# SDP21_Main_Board_Schematic.net
KiCad netlist of a schematic drawn in Altium Designer
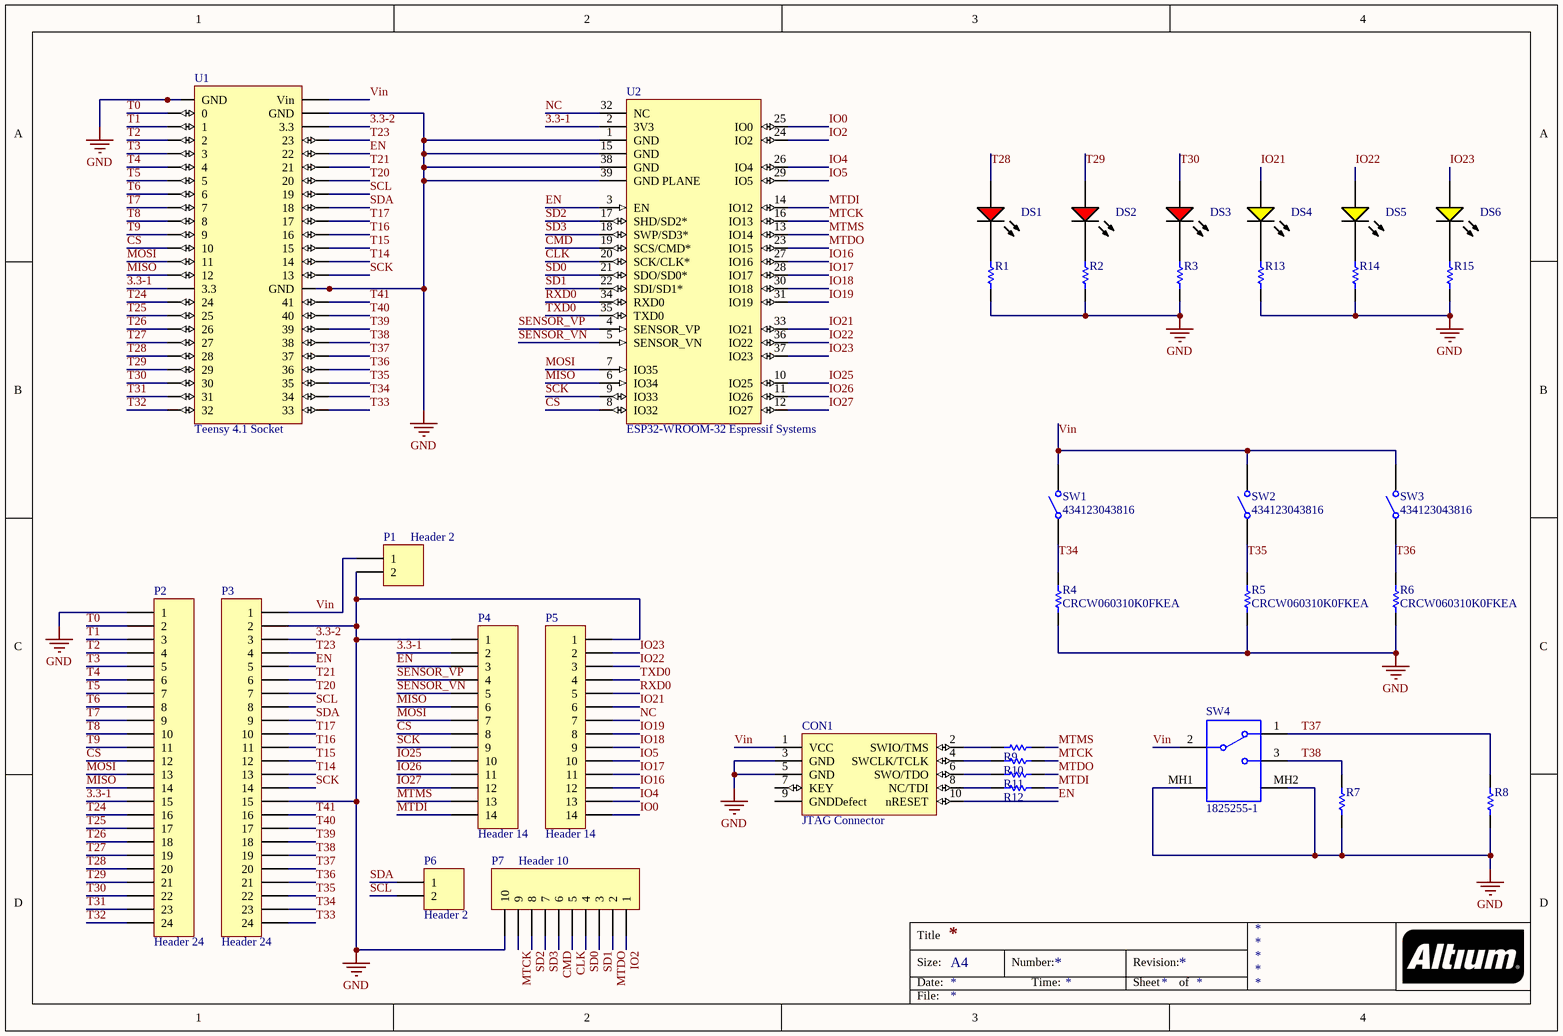
[diagram p0: SDP21_Main_Board_Schematic.SchDoc]

(export (version "E")
  (design (tool "Eeschema 10.0.6"))
  (components
    (comp (ref "CON1")
      (value "JTAG Connector")
      (footprint "5x2 - 50mil")
      (libsource (lib "SDP21_Main_Board_Schematic_Library") (part "JTAG Connector"))
    )
    (comp (ref "DS1")
      (value "TLMS1000-GS08")
      (footprint "VISH-TLMS1000_V")
      (description "Low Current LED, 40 mW, 1.8 V, -40 to 100 degC, 2-Pin SMD (0603), RoHS, Tape and Reel")
      (fields (field (name "MANUFACTURER") "Vishay"))
      (libsource (lib "Altium Content Vault") (part "LED-RED-AK-2"))
    )
    (comp (ref "DS2")
      (value "TLMS1000-GS08")
      (footprint "VISH-TLMS1000_V")
      (description "Low Current LED, 40 mW, 1.8 V, -40 to 100 degC, 2-Pin SMD (0603), RoHS, Tape and Reel")
      (fields (field (name "MANUFACTURER") "Vishay"))
      (libsource (lib "Altium Content Vault") (part "LED-RED-AK-2"))
    )
    (comp (ref "DS3")
      (value "TLMS1000-GS08")
      (footprint "VISH-TLMS1000_V")
      (description "Low Current LED, 40 mW, 1.8 V, -40 to 100 degC, 2-Pin SMD (0603), RoHS, Tape and Reel")
      (fields (field (name "MANUFACTURER") "Vishay"))
      (libsource (lib "Altium Content Vault") (part "LED-RED-AK-2"))
    )
    (comp (ref "DS4")
      (value "TLMY1000-GS08")
      (footprint "VISH-TLMY1000_V")
      (description "Low Current LED, 40 mW, -40 to 100 degC, 2-Pin SMD, RoHS, Tape and Reel")
      (fields (field (name "MANUFACTURER") "Vishay"))
      (libsource (lib "Altium Content Vault") (part "LED-YELLOW-AK-2"))
    )
    (comp (ref "DS5")
      (value "TLMY1000-GS08")
      (footprint "VISH-TLMY1000_V")
      (description "Low Current LED, 40 mW, -40 to 100 degC, 2-Pin SMD, RoHS, Tape and Reel")
      (fields (field (name "MANUFACTURER") "Vishay"))
      (libsource (lib "Altium Content Vault") (part "LED-YELLOW-AK-2"))
    )
    (comp (ref "DS6")
      (value "TLMY1000-GS08")
      (footprint "VISH-TLMY1000_V")
      (description "Low Current LED, 40 mW, -40 to 100 degC, 2-Pin SMD, RoHS, Tape and Reel")
      (fields (field (name "MANUFACTURER") "Vishay"))
      (libsource (lib "Altium Content Vault") (part "LED-YELLOW-AK-2"))
    )
    (comp (ref "P1")
      (value "Header 2")
      (footprint "HDR1X2")
      (description "Header, 2-Pin")
      (fields (field (name "PUBLISHER") "Altium Limited"))
      (libsource (lib "Miscellaneous Connectors") (part "Header 2"))
    )
    (comp (ref "P2")
      (value "Header 24")
      (footprint "HDR1X24")
      (description "Header, 24-Pin")
      (fields (field (name "PUBLISHER") "Altium Limited"))
      (libsource (lib "") (part "Header 24_1"))
    )
    (comp (ref "P3")
      (value "Header 24")
      (footprint "HDR1X24")
      (description "Header, 24-Pin")
      (fields (field (name "PUBLISHER") "Altium Limited"))
      (libsource (lib "Miscellaneous Connectors") (part "Header 24"))
    )
    (comp (ref "P4")
      (value "Header 14")
      (footprint "HDR1X14")
      (description "Header, 14-Pin")
      (fields (field (name "PUBLISHER") "Altium Limited"))
      (libsource (lib "") (part "Header 14_1"))
    )
    (comp (ref "P5")
      (value "Header 14")
      (footprint "HDR1X14")
      (description "Header, 14-Pin")
      (fields (field (name "PUBLISHER") "Altium Limited"))
      (libsource (lib "Miscellaneous Connectors") (part "Header 14"))
    )
    (comp (ref "P6")
      (value "Header 2")
      (footprint "HDR1X2")
      (description "Header, 2-Pin")
      (fields (field (name "PUBLISHER") "Altium Limited"))
      (libsource (lib "Miscellaneous Connectors") (part "Header 2"))
    )
    (comp (ref "P7")
      (value "Header 10")
      (footprint "HDR1X10")
      (description "Header, 10-Pin")
      (fields (field (name "PUBLISHER") "Altium Limited"))
      (libsource (lib "Miscellaneous Connectors") (part "Header 10"))
    )
    (comp (ref "R1")
      (value "RR1220P-331-D")
      (footprint "RESC2013X50X40LL20T20")
      (fields (field (name "MANUFACTURER") "Susumu"))
      (libsource (lib "Altium Content Vault") (part "RES"))
    )
    (comp (ref "R2")
      (value "RR1220P-331-D")
      (footprint "RESC2013X50X40LL20T20")
      (fields (field (name "MANUFACTURER") "Susumu"))
      (libsource (lib "Altium Content Vault") (part "RES"))
    )
    (comp (ref "R3")
      (value "RR1220P-331-D")
      (footprint "RESC2013X50X40LL20T20")
      (fields (field (name "MANUFACTURER") "Susumu"))
      (libsource (lib "Altium Content Vault") (part "RES"))
    )
    (comp (ref "R4")
      (value "CRCW060310K0FKEA")
      (footprint "RESC1609X50X30NL8T20")
      (description "Chip Resistor, 10 KOhm, +/- 1%, 100 mW, -55 to 155 degC, 0603 (1608 Metric), RoHS, Tape and Reel")
      (fields (field (name "MANUFACTURER") "Vishay Semiconductor"))
      (libsource (lib "Altium Content Vault") (part "RES-2"))
    )
    (comp (ref "R5")
      (value "CRCW060310K0FKEA")
      (footprint "RESC1609X50X30NL8T20")
      (description "Chip Resistor, 10 KOhm, +/- 1%, 100 mW, -55 to 155 degC, 0603 (1608 Metric), RoHS, Tape and Reel")
      (fields (field (name "MANUFACTURER") "Vishay Semiconductor"))
      (libsource (lib "Altium Content Vault") (part "RES-2"))
    )
    (comp (ref "R6")
      (value "CRCW060310K0FKEA")
      (footprint "RESC1609X50X30NL8T20")
      (description "Chip Resistor, 10 KOhm, +/- 1%, 100 mW, -55 to 155 degC, 0603 (1608 Metric), RoHS, Tape and Reel")
      (fields (field (name "MANUFACTURER") "Vishay Semiconductor"))
      (libsource (lib "Altium Content Vault") (part "RES-2"))
    )
    (comp (ref "R7")
      (value "CRCW060310K0FKEA")
      (footprint "RESC1609X50X30NL8T20")
      (description "Chip Resistor, 10 KOhm, +/- 1%, 100 mW, -55 to 155 degC, 0603 (1608 Metric), RoHS, Tape and Reel")
      (fields (field (name "MANUFACTURER") "Vishay Semiconductor"))
      (libsource (lib "Altium Content Vault") (part "RES-2"))
    )
    (comp (ref "R8")
      (value "CRCW060310K0FKEA")
      (footprint "RESC1609X50X30NL8T20")
      (description "Chip Resistor, 10 KOhm, +/- 1%, 100 mW, -55 to 155 degC, 0603 (1608 Metric), RoHS, Tape and Reel")
      (fields (field (name "MANUFACTURER") "Vishay Semiconductor"))
      (libsource (lib "Altium Content Vault") (part "RES-2"))
    )
    (comp (ref "R9")
      (value "CRCW0603100RFKEA")
      (footprint "RESC1609X50X30NL10T20")
      (fields (field (name "MANUFACTURER") "Vishay Dale"))
      (libsource (lib "Altium Content Vault") (part "RES"))
    )
    (comp (ref "R10")
      (value "CRCW0603100RFKEA")
      (footprint "RESC1609X50X30NL10T20")
      (fields (field (name "MANUFACTURER") "Vishay Dale"))
      (libsource (lib "Altium Content Vault") (part "RES"))
    )
    (comp (ref "R11")
      (value "CRCW0603100RFKEA")
      (footprint "RESC1609X50X30NL10T20")
      (fields (field (name "MANUFACTURER") "Vishay Dale"))
      (libsource (lib "Altium Content Vault") (part "RES"))
    )
    (comp (ref "R12")
      (value "CRCW0603100RFKEA")
      (footprint "RESC1609X50X30NL10T20")
      (fields (field (name "MANUFACTURER") "Vishay Dale"))
      (libsource (lib "Altium Content Vault") (part "RES"))
    )
    (comp (ref "R13")
      (value "RR1220P-331-D")
      (footprint "RESC2013X50X40LL20T20")
      (fields (field (name "MANUFACTURER") "Susumu"))
      (libsource (lib "Altium Content Vault") (part "RES"))
    )
    (comp (ref "R14")
      (value "RR1220P-331-D")
      (footprint "RESC2013X50X40LL20T20")
      (fields (field (name "MANUFACTURER") "Susumu"))
      (libsource (lib "Altium Content Vault") (part "RES"))
    )
    (comp (ref "R15")
      (value "RR1220P-331-D")
      (footprint "RESC2013X50X40LL20T20")
      (fields (field (name "MANUFACTURER") "Susumu"))
      (libsource (lib "Altium Content Vault") (part "RES"))
    )
    (comp (ref "SW1")
      (value "434123043816")
      (footprint "434123043816")
      (description "WS-TASV J-Bend SMD Tact Switch 6.0X3.5 mm")
      (fields (field (name "MANUFACTURER") "Wuerth Elektronik"))
      (libsource (lib "Altium Content Vault") (part "WE-TACT-SW-2"))
    )
    (comp (ref "SW2")
      (value "434123043816")
      (footprint "434123043816")
      (description "WS-TASV J-Bend SMD Tact Switch 6.0X3.5 mm")
      (fields (field (name "MANUFACTURER") "Wuerth Elektronik"))
      (libsource (lib "Altium Content Vault") (part "WE-TACT-SW-2"))
    )
    (comp (ref "SW3")
      (value "434123043816")
      (footprint "434123043816")
      (description "WS-TASV J-Bend SMD Tact Switch 6.0X3.5 mm")
      (fields (field (name "MANUFACTURER") "Wuerth Elektronik"))
      (libsource (lib "Altium Content Vault") (part "WE-TACT-SW-2"))
    )
    (comp (ref "SW4")
      (value "1825255-1")
      (footprint "TECO-1825255-1_V")
      (description "Slide Switch, SPDT, 125 V, -20 to 85 degC, 5-Pin THD, RoHS, Tray")
      (fields (field (name "MANUFACTURER") "TE Connectivity"))
      (libsource (lib "Altium Content Vault") (part "SW-SPDT-3_C"))
    )
    (comp (ref "U1")
      (value "Teensy 4.1 Socket")
      (footprint "Teensy 4.1 Socket")
      (description "Teensy 4.1")
      (libsource (lib "SDP21_Main_Board_Schematic_Library") (part "Teensy 4.1 Socket"))
    )
    (comp (ref "U2")
      (value "ESP32-WROOM-32 Espressif Systems")
      (footprint "Espressif ESP32 Castellated")
      (description "ESP32 BGA mounted on PCB w/ castellated holes")
      (libsource (lib "SDP21_Main_Board_Schematic_Library") (part "ESP32-WROOM-32 Espressif Systems"))
    )
  )
  (nets
    (net (code "1") (name "/3.3-1") (class "Default")
      (node (ref "P2") (pin "15") (pinfunction "15_15") (pintype "passive"))
      (node (ref "P4") (pin "2") (pinfunction "2_2") (pintype "passive"))
      (node (ref "U1") (pin "3.3-1") (pinfunction "3.3_3.3-1") (pintype "power_in"))
      (node (ref "U2") (pin "2") (pinfunction "3V3_2") (pintype "power_in"))
    )
    (net (code "2") (name "/3.3-2") (class "Default")
      (node (ref "P3") (pin "3") (pinfunction "3_3") (pintype "passive"))
      (node (ref "U1") (pin "3.3-2") (pinfunction "3.3_3.3-2") (pintype "power_in"))
    )
    (net (code "3") (name "/CLK") (class "Default")
      (node (ref "P7") (pin "5") (pinfunction "5_5") (pintype "passive"))
      (node (ref "U2") (pin "20") (pinfunction "SCK/CLK*_20") (pintype "bidirectional"))
    )
    (net (code "4") (name "/CMD") (class "Default")
      (node (ref "P7") (pin "6") (pinfunction "6_6") (pintype "passive"))
      (node (ref "U2") (pin "19") (pinfunction "SCS/CMD*_19") (pintype "bidirectional"))
    )
    (net (code "5") (name "/CS") (class "Default")
      (node (ref "P2") (pin "12") (pinfunction "12_12") (pintype "passive"))
      (node (ref "P4") (pin "8") (pinfunction "8_8") (pintype "passive"))
      (node (ref "U1") (pin "10") (pinfunction "10_10") (pintype "bidirectional"))
      (node (ref "U2") (pin "8") (pinfunction "IO32_8") (pintype "bidirectional"))
    )
    (net (code "6") (name "/EN") (class "Default")
      (node (ref "CON1") (pin "10") (pinfunction "nRESET_10") (pintype "bidirectional"))
      (node (ref "P3") (pin "5") (pinfunction "5_5") (pintype "passive"))
      (node (ref "P4") (pin "3") (pinfunction "3_3") (pintype "passive"))
      (node (ref "U1") (pin "22") (pinfunction "22_22") (pintype "bidirectional"))
      (node (ref "U2") (pin "3") (pinfunction "EN_3") (pintype "input"))
    )
    (net (code "7") (name "/IO0") (class "Default")
      (node (ref "P5") (pin "14") (pinfunction "14_14") (pintype "passive"))
      (node (ref "U2") (pin "25") (pinfunction "IO0_25") (pintype "bidirectional"))
    )
    (net (code "8") (name "/IO2") (class "Default")
      (node (ref "P7") (pin "1") (pinfunction "1_1") (pintype "passive"))
      (node (ref "U2") (pin "24") (pinfunction "IO2_24") (pintype "bidirectional"))
    )
    (net (code "9") (name "/IO4") (class "Default")
      (node (ref "P5") (pin "13") (pinfunction "13_13") (pintype "passive"))
      (node (ref "U2") (pin "26") (pinfunction "IO4_26") (pintype "bidirectional"))
    )
    (net (code "10") (name "/IO5") (class "Default")
      (node (ref "P5") (pin "10") (pinfunction "10_10") (pintype "passive"))
      (node (ref "U2") (pin "29") (pinfunction "IO5_29") (pintype "bidirectional"))
    )
    (net (code "11") (name "/IO16") (class "Default")
      (node (ref "P5") (pin "12") (pinfunction "12_12") (pintype "passive"))
      (node (ref "U2") (pin "27") (pinfunction "IO16_27") (pintype "bidirectional"))
    )
    (net (code "12") (name "/IO17") (class "Default")
      (node (ref "P5") (pin "11") (pinfunction "11_11") (pintype "passive"))
      (node (ref "U2") (pin "28") (pinfunction "IO17_28") (pintype "bidirectional"))
    )
    (net (code "13") (name "/IO18") (class "Default")
      (node (ref "P5") (pin "9") (pinfunction "9_9") (pintype "passive"))
      (node (ref "U2") (pin "30") (pinfunction "IO18_30") (pintype "bidirectional"))
    )
    (net (code "14") (name "/IO19") (class "Default")
      (node (ref "P5") (pin "8") (pinfunction "8_8") (pintype "passive"))
      (node (ref "U2") (pin "31") (pinfunction "IO19_31") (pintype "bidirectional"))
    )
    (net (code "15") (name "/IO21") (class "Default")
      (node (ref "DS4") (pin "1") (pinfunction "A_1") (pintype "passive"))
      (node (ref "P5") (pin "6") (pinfunction "6_6") (pintype "passive"))
      (node (ref "U2") (pin "33") (pinfunction "IO21_33") (pintype "bidirectional"))
    )
    (net (code "16") (name "/IO22") (class "Default")
      (node (ref "DS5") (pin "1") (pinfunction "A_1") (pintype "passive"))
      (node (ref "P5") (pin "3") (pinfunction "3_3") (pintype "passive"))
      (node (ref "U2") (pin "36") (pinfunction "IO22_36") (pintype "bidirectional"))
    )
    (net (code "17") (name "/IO23") (class "Default")
      (node (ref "DS6") (pin "1") (pinfunction "A_1") (pintype "passive"))
      (node (ref "P5") (pin "2") (pinfunction "2_2") (pintype "passive"))
      (node (ref "U2") (pin "37") (pinfunction "IO23_37") (pintype "bidirectional"))
    )
    (net (code "18") (name "/IO25") (class "Default")
      (node (ref "P4") (pin "10") (pinfunction "10_10") (pintype "passive"))
      (node (ref "U2") (pin "10") (pinfunction "IO25_10") (pintype "bidirectional"))
    )
    (net (code "19") (name "/IO26") (class "Default")
      (node (ref "P4") (pin "11") (pinfunction "11_11") (pintype "passive"))
      (node (ref "U2") (pin "11") (pinfunction "IO26_11") (pintype "bidirectional"))
    )
    (net (code "20") (name "/IO27") (class "Default")
      (node (ref "P4") (pin "12") (pinfunction "12_12") (pintype "passive"))
      (node (ref "U2") (pin "12") (pinfunction "IO27_12") (pintype "bidirectional"))
    )
    (net (code "21") (name "/MISO") (class "Default")
      (node (ref "P2") (pin "14") (pinfunction "14_14") (pintype "passive"))
      (node (ref "P4") (pin "6") (pinfunction "6_6") (pintype "passive"))
      (node (ref "U1") (pin "12") (pinfunction "12_12") (pintype "bidirectional"))
      (node (ref "U2") (pin "6") (pinfunction "IO34_6") (pintype "input"))
    )
    (net (code "22") (name "/MOSI") (class "Default")
      (node (ref "P2") (pin "13") (pinfunction "13_13") (pintype "passive"))
      (node (ref "P4") (pin "7") (pinfunction "7_7") (pintype "passive"))
      (node (ref "U1") (pin "11") (pinfunction "11_11") (pintype "bidirectional"))
      (node (ref "U2") (pin "7") (pinfunction "IO35_7") (pintype "input"))
    )
    (net (code "23") (name "/MTCK") (class "Default")
      (node (ref "P7") (pin "9") (pinfunction "9_9") (pintype "passive"))
      (node (ref "R10") (pin "2") (pinfunction "2_2") (pintype "passive"))
      (node (ref "U2") (pin "16") (pinfunction "IO13_16") (pintype "bidirectional"))
    )
    (net (code "24") (name "/MTDI") (class "Default")
      (node (ref "P4") (pin "14") (pinfunction "14_14") (pintype "passive"))
      (node (ref "R12") (pin "2") (pinfunction "2_2") (pintype "passive"))
      (node (ref "U2") (pin "14") (pinfunction "IO12_14") (pintype "bidirectional"))
    )
    (net (code "25") (name "/MTDO") (class "Default")
      (node (ref "P7") (pin "2") (pinfunction "2_2") (pintype "passive"))
      (node (ref "R11") (pin "2") (pinfunction "2_2") (pintype "passive"))
      (node (ref "U2") (pin "23") (pinfunction "IO15_23") (pintype "bidirectional"))
    )
    (net (code "26") (name "/MTMS") (class "Default")
      (node (ref "P4") (pin "13") (pinfunction "13_13") (pintype "passive"))
      (node (ref "R9") (pin "2") (pinfunction "2_2") (pintype "passive"))
      (node (ref "U2") (pin "13") (pinfunction "IO14_13") (pintype "bidirectional"))
    )
    (net (code "27") (name "/NC") (class "Default")
      (node (ref "P5") (pin "7") (pinfunction "7_7") (pintype "passive"))
      (node (ref "U2") (pin "32") (pinfunction "NC_32") (pintype "passive"))
    )
    (net (code "28") (name "/RXD0") (class "Default")
      (node (ref "P5") (pin "5") (pinfunction "5_5") (pintype "passive"))
      (node (ref "U2") (pin "34") (pinfunction "RXD0_34") (pintype "bidirectional"))
    )
    (net (code "29") (name "/SCK") (class "Default")
      (node (ref "P3") (pin "14") (pinfunction "14_14") (pintype "passive"))
      (node (ref "P4") (pin "9") (pinfunction "9_9") (pintype "passive"))
      (node (ref "U1") (pin "13") (pinfunction "13_13") (pintype "bidirectional"))
      (node (ref "U2") (pin "9") (pinfunction "IO33_9") (pintype "bidirectional"))
    )
    (net (code "30") (name "/SCL") (class "Default")
      (node (ref "P3") (pin "8") (pinfunction "8_8") (pintype "passive"))
      (node (ref "P6") (pin "2") (pinfunction "2_2") (pintype "passive"))
      (node (ref "U1") (pin "19") (pinfunction "19_19") (pintype "bidirectional"))
    )
    (net (code "31") (name "/SD0") (class "Default")
      (node (ref "P7") (pin "4") (pinfunction "4_4") (pintype "passive"))
      (node (ref "U2") (pin "21") (pinfunction "SDO/SD0*_21") (pintype "bidirectional"))
    )
    (net (code "32") (name "/SD1") (class "Default")
      (node (ref "P7") (pin "3") (pinfunction "3_3") (pintype "passive"))
      (node (ref "U2") (pin "22") (pinfunction "SDI/SD1*_22") (pintype "bidirectional"))
    )
    (net (code "33") (name "/SD2") (class "Default")
      (node (ref "P7") (pin "8") (pinfunction "8_8") (pintype "passive"))
      (node (ref "U2") (pin "17") (pinfunction "SHD/SD2*_17") (pintype "bidirectional"))
    )
    (net (code "34") (name "/SD3") (class "Default")
      (node (ref "P7") (pin "7") (pinfunction "7_7") (pintype "passive"))
      (node (ref "U2") (pin "18") (pinfunction "SWP/SD3*_18") (pintype "bidirectional"))
    )
    (net (code "35") (name "/SDA") (class "Default")
      (node (ref "P3") (pin "9") (pinfunction "9_9") (pintype "passive"))
      (node (ref "P6") (pin "1") (pinfunction "1_1") (pintype "passive"))
      (node (ref "U1") (pin "18") (pinfunction "18_18") (pintype "bidirectional"))
    )
    (net (code "36") (name "/SENSOR_VN") (class "Default")
      (node (ref "P4") (pin "5") (pinfunction "5_5") (pintype "passive"))
      (node (ref "U2") (pin "5") (pinfunction "SENSOR_VN_5") (pintype "input"))
    )
    (net (code "37") (name "/SENSOR_VP") (class "Default")
      (node (ref "P4") (pin "4") (pinfunction "4_4") (pintype "passive"))
      (node (ref "U2") (pin "4") (pinfunction "SENSOR_VP_4") (pintype "input"))
    )
    (net (code "38") (name "/T0") (class "Default")
      (node (ref "P2") (pin "2") (pinfunction "2_2") (pintype "passive"))
      (node (ref "U1") (pin "0") (pinfunction "0_0") (pintype "bidirectional"))
    )
    (net (code "39") (name "/T1") (class "Default")
      (node (ref "P2") (pin "3") (pinfunction "3_3") (pintype "passive"))
      (node (ref "U1") (pin "1") (pinfunction "1_1") (pintype "bidirectional"))
    )
    (net (code "40") (name "/T2") (class "Default")
      (node (ref "P2") (pin "4") (pinfunction "4_4") (pintype "passive"))
      (node (ref "U1") (pin "2") (pinfunction "2_2") (pintype "bidirectional"))
    )
    (net (code "41") (name "/T3") (class "Default")
      (node (ref "P2") (pin "5") (pinfunction "5_5") (pintype "passive"))
      (node (ref "U1") (pin "3") (pinfunction "3_3") (pintype "bidirectional"))
    )
    (net (code "42") (name "/T4") (class "Default")
      (node (ref "P2") (pin "6") (pinfunction "6_6") (pintype "passive"))
      (node (ref "U1") (pin "4") (pinfunction "4_4") (pintype "bidirectional"))
    )
    (net (code "43") (name "/T5") (class "Default")
      (node (ref "P2") (pin "7") (pinfunction "7_7") (pintype "passive"))
      (node (ref "U1") (pin "5") (pinfunction "5_5") (pintype "bidirectional"))
    )
    (net (code "44") (name "/T6") (class "Default")
      (node (ref "P2") (pin "8") (pinfunction "8_8") (pintype "passive"))
      (node (ref "U1") (pin "6") (pinfunction "6_6") (pintype "bidirectional"))
    )
    (net (code "45") (name "/T7") (class "Default")
      (node (ref "P2") (pin "9") (pinfunction "9_9") (pintype "passive"))
      (node (ref "U1") (pin "7") (pinfunction "7_7") (pintype "bidirectional"))
    )
    (net (code "46") (name "/T8") (class "Default")
      (node (ref "P2") (pin "10") (pinfunction "10_10") (pintype "passive"))
      (node (ref "U1") (pin "8") (pinfunction "8_8") (pintype "bidirectional"))
    )
    (net (code "47") (name "/T9") (class "Default")
      (node (ref "P2") (pin "11") (pinfunction "11_11") (pintype "passive"))
      (node (ref "U1") (pin "9") (pinfunction "9_9") (pintype "bidirectional"))
    )
    (net (code "48") (name "/T14") (class "Default")
      (node (ref "P3") (pin "13") (pinfunction "13_13") (pintype "passive"))
      (node (ref "U1") (pin "14") (pinfunction "14_14") (pintype "bidirectional"))
    )
    (net (code "49") (name "/T15") (class "Default")
      (node (ref "P3") (pin "12") (pinfunction "12_12") (pintype "passive"))
      (node (ref "U1") (pin "15") (pinfunction "15_15") (pintype "bidirectional"))
    )
    (net (code "50") (name "/T16") (class "Default")
      (node (ref "P3") (pin "11") (pinfunction "11_11") (pintype "passive"))
      (node (ref "U1") (pin "16") (pinfunction "16_16") (pintype "bidirectional"))
    )
    (net (code "51") (name "/T17") (class "Default")
      (node (ref "P3") (pin "10") (pinfunction "10_10") (pintype "passive"))
      (node (ref "U1") (pin "17") (pinfunction "17_17") (pintype "bidirectional"))
    )
    (net (code "52") (name "/T20") (class "Default")
      (node (ref "P3") (pin "7") (pinfunction "7_7") (pintype "passive"))
      (node (ref "U1") (pin "20") (pinfunction "20_20") (pintype "bidirectional"))
    )
    (net (code "53") (name "/T21") (class "Default")
      (node (ref "P3") (pin "6") (pinfunction "6_6") (pintype "passive"))
      (node (ref "U1") (pin "21") (pinfunction "21_21") (pintype "bidirectional"))
    )
    (net (code "54") (name "/T23") (class "Default")
      (node (ref "P3") (pin "4") (pinfunction "4_4") (pintype "passive"))
      (node (ref "U1") (pin "23") (pinfunction "23_23") (pintype "bidirectional"))
    )
    (net (code "55") (name "/T24") (class "Default")
      (node (ref "P2") (pin "16") (pinfunction "16_16") (pintype "passive"))
      (node (ref "U1") (pin "24") (pinfunction "24_24") (pintype "bidirectional"))
    )
    (net (code "56") (name "/T25") (class "Default")
      (node (ref "P2") (pin "17") (pinfunction "17_17") (pintype "passive"))
      (node (ref "U1") (pin "25") (pinfunction "25_25") (pintype "bidirectional"))
    )
    (net (code "57") (name "/T26") (class "Default")
      (node (ref "P2") (pin "18") (pinfunction "18_18") (pintype "passive"))
      (node (ref "U1") (pin "26") (pinfunction "26_26") (pintype "bidirectional"))
    )
    (net (code "58") (name "/T27") (class "Default")
      (node (ref "P2") (pin "19") (pinfunction "19_19") (pintype "passive"))
      (node (ref "U1") (pin "27") (pinfunction "27_27") (pintype "bidirectional"))
    )
    (net (code "59") (name "/T28") (class "Default")
      (node (ref "DS1") (pin "1") (pinfunction "A_1") (pintype "passive"))
      (node (ref "P2") (pin "20") (pinfunction "20_20") (pintype "passive"))
      (node (ref "U1") (pin "28") (pinfunction "28_28") (pintype "bidirectional"))
    )
    (net (code "60") (name "/T29") (class "Default")
      (node (ref "DS2") (pin "1") (pinfunction "A_1") (pintype "passive"))
      (node (ref "P2") (pin "21") (pinfunction "21_21") (pintype "passive"))
      (node (ref "U1") (pin "29") (pinfunction "29_29") (pintype "bidirectional"))
    )
    (net (code "61") (name "/T30") (class "Default")
      (node (ref "DS3") (pin "1") (pinfunction "A_1") (pintype "passive"))
      (node (ref "P2") (pin "22") (pinfunction "22_22") (pintype "passive"))
      (node (ref "U1") (pin "30") (pinfunction "30_30") (pintype "bidirectional"))
    )
    (net (code "62") (name "/T31") (class "Default")
      (node (ref "P2") (pin "23") (pinfunction "23_23") (pintype "passive"))
      (node (ref "U1") (pin "31") (pinfunction "31_31") (pintype "bidirectional"))
    )
    (net (code "63") (name "/T32") (class "Default")
      (node (ref "P2") (pin "24") (pinfunction "24_24") (pintype "passive"))
      (node (ref "U1") (pin "32") (pinfunction "32_32") (pintype "bidirectional"))
    )
    (net (code "64") (name "/T33") (class "Default")
      (node (ref "P3") (pin "24") (pinfunction "24_24") (pintype "passive"))
      (node (ref "U1") (pin "33") (pinfunction "33_33") (pintype "bidirectional"))
    )
    (net (code "65") (name "/T34") (class "Default")
      (node (ref "P3") (pin "23") (pinfunction "23_23") (pintype "passive"))
      (node (ref "R4") (pin "2") (pinfunction "2_2") (pintype "passive"))
      (node (ref "SW1") (pin "1") (pinfunction "1_1") (pintype "passive"))
      (node (ref "U1") (pin "34") (pinfunction "34_34") (pintype "bidirectional"))
    )
    (net (code "66") (name "/T35") (class "Default")
      (node (ref "P3") (pin "22") (pinfunction "22_22") (pintype "passive"))
      (node (ref "R5") (pin "2") (pinfunction "2_2") (pintype "passive"))
      (node (ref "SW2") (pin "1") (pinfunction "1_1") (pintype "passive"))
      (node (ref "U1") (pin "35") (pinfunction "35_35") (pintype "bidirectional"))
    )
    (net (code "67") (name "/T36") (class "Default")
      (node (ref "P3") (pin "21") (pinfunction "21_21") (pintype "passive"))
      (node (ref "R6") (pin "2") (pinfunction "2_2") (pintype "passive"))
      (node (ref "SW3") (pin "1") (pinfunction "1_1") (pintype "passive"))
      (node (ref "U1") (pin "36") (pinfunction "36_36") (pintype "bidirectional"))
    )
    (net (code "68") (name "/T37") (class "Default")
      (node (ref "P3") (pin "20") (pinfunction "20_20") (pintype "passive"))
      (node (ref "R8") (pin "2") (pinfunction "2_2") (pintype "passive"))
      (node (ref "SW4") (pin "1") (pinfunction "1_1") (pintype "passive"))
      (node (ref "U1") (pin "37") (pinfunction "37_37") (pintype "bidirectional"))
    )
    (net (code "69") (name "/T38") (class "Default")
      (node (ref "P3") (pin "19") (pinfunction "19_19") (pintype "passive"))
      (node (ref "R7") (pin "2") (pinfunction "2_2") (pintype "passive"))
      (node (ref "SW4") (pin "3") (pinfunction "3_3") (pintype "passive"))
      (node (ref "U1") (pin "38") (pinfunction "38_38") (pintype "bidirectional"))
    )
    (net (code "70") (name "/T39") (class "Default")
      (node (ref "P3") (pin "18") (pinfunction "18_18") (pintype "passive"))
      (node (ref "U1") (pin "39") (pinfunction "39_39") (pintype "bidirectional"))
    )
    (net (code "71") (name "/T40") (class "Default")
      (node (ref "P3") (pin "17") (pinfunction "17_17") (pintype "passive"))
      (node (ref "U1") (pin "40") (pinfunction "40_40") (pintype "bidirectional"))
    )
    (net (code "72") (name "/T41") (class "Default")
      (node (ref "P3") (pin "16") (pinfunction "16_16") (pintype "passive"))
      (node (ref "U1") (pin "41") (pinfunction "41_41") (pintype "bidirectional"))
    )
    (net (code "73") (name "/TXD0") (class "Default")
      (node (ref "P5") (pin "4") (pinfunction "4_4") (pintype "passive"))
      (node (ref "U2") (pin "35") (pinfunction "TXD0_35") (pintype "bidirectional"))
    )
    (net (code "74") (name "/Vin") (class "Default")
      (node (ref "CON1") (pin "1") (pinfunction "VCC_1") (pintype "power_in"))
      (node (ref "P1") (pin "1") (pinfunction "1_1") (pintype "passive"))
      (node (ref "P3") (pin "1") (pinfunction "1_1") (pintype "passive"))
      (node (ref "SW1") (pin "2") (pinfunction "2_2") (pintype "passive"))
      (node (ref "SW2") (pin "2") (pinfunction "2_2") (pintype "passive"))
      (node (ref "SW3") (pin "2") (pinfunction "2_2") (pintype "passive"))
      (node (ref "SW4") (pin "2") (pinfunction "2_2") (pintype "passive"))
      (node (ref "U1") (pin "Vin") (pinfunction "Vin_Vin") (pintype "power_in"))
    )
    (net (code "75") (name "GND") (class "Default")
      (node (ref "CON1") (pin "3") (pinfunction "GND_3") (pintype "power_in"))
      (node (ref "CON1") (pin "5") (pinfunction "GND_5") (pintype "power_in"))
      (node (ref "P1") (pin "2") (pinfunction "2_2") (pintype "passive"))
      (node (ref "P2") (pin "1") (pinfunction "1_1") (pintype "passive"))
      (node (ref "P3") (pin "15") (pinfunction "15_15") (pintype "passive"))
      (node (ref "P3") (pin "2") (pinfunction "2_2") (pintype "passive"))
      (node (ref "P4") (pin "1") (pinfunction "1_1") (pintype "passive"))
      (node (ref "P5") (pin "1") (pinfunction "1_1") (pintype "passive"))
      (node (ref "P7") (pin "10") (pinfunction "10_10") (pintype "passive"))
      (node (ref "R1") (pin "1") (pinfunction "1_1") (pintype "passive"))
      (node (ref "R13") (pin "1") (pinfunction "1_1") (pintype "passive"))
      (node (ref "R14") (pin "1") (pinfunction "1_1") (pintype "passive"))
      (node (ref "R15") (pin "1") (pinfunction "1_1") (pintype "passive"))
      (node (ref "R2") (pin "1") (pinfunction "1_1") (pintype "passive"))
      (node (ref "R3") (pin "1") (pinfunction "1_1") (pintype "passive"))
      (node (ref "R4") (pin "1") (pinfunction "1_1") (pintype "passive"))
      (node (ref "R5") (pin "1") (pinfunction "1_1") (pintype "passive"))
      (node (ref "R6") (pin "1") (pinfunction "1_1") (pintype "passive"))
      (node (ref "R7") (pin "1") (pinfunction "1_1") (pintype "passive"))
      (node (ref "R8") (pin "1") (pinfunction "1_1") (pintype "passive"))
      (node (ref "SW4") (pin "MH1") (pinfunction "MH1_MH1") (pintype "passive"))
      (node (ref "SW4") (pin "MH2") (pinfunction "MH2_MH2") (pintype "passive"))
      (node (ref "U1") (pin "GND1") (pinfunction "GND_GND1") (pintype "power_in"))
      (node (ref "U1") (pin "GND2") (pinfunction "GND_GND2") (pintype "power_in"))
      (node (ref "U1") (pin "GND3") (pinfunction "GND_GND3") (pintype "power_in"))
      (node (ref "U2") (pin "1") (pinfunction "GND_1") (pintype "power_in"))
      (node (ref "U2") (pin "15") (pinfunction "GND_15") (pintype "power_in"))
      (node (ref "U2") (pin "38") (pinfunction "GND_38") (pintype "power_in"))
      (node (ref "U2") (pin "39") (pinfunction "GND_PLANE_39") (pintype "power_in"))
    )
    (net (code "76") (name "Net-(CON1-NC{slash}TDI)") (class "Default")
      (node (ref "CON1") (pin "8") (pinfunction "NC/TDI_8") (pintype "bidirectional"))
      (node (ref "R12") (pin "1") (pinfunction "1_1") (pintype "passive"))
    )
    (net (code "77") (name "Net-(CON1-SWCLK{slash}TCLK)") (class "Default")
      (node (ref "CON1") (pin "4") (pinfunction "SWCLK/TCLK_4") (pintype "bidirectional"))
      (node (ref "R10") (pin "1") (pinfunction "1_1") (pintype "passive"))
    )
    (net (code "78") (name "Net-(CON1-SWIO{slash}TMS)") (class "Default")
      (node (ref "CON1") (pin "2") (pinfunction "SWIO/TMS_2") (pintype "bidirectional"))
      (node (ref "R9") (pin "1") (pinfunction "1_1") (pintype "passive"))
    )
    (net (code "79") (name "Net-(CON1-SWO{slash}TDO)") (class "Default")
      (node (ref "CON1") (pin "6") (pinfunction "SWO/TDO_6") (pintype "bidirectional"))
      (node (ref "R11") (pin "1") (pinfunction "1_1") (pintype "passive"))
    )
    (net (code "80") (name "Net-(DS1-K)") (class "Default")
      (node (ref "DS1") (pin "2") (pinfunction "K_2") (pintype "passive"))
      (node (ref "R1") (pin "2") (pinfunction "2_2") (pintype "passive"))
    )
    (net (code "81") (name "Net-(DS2-K)") (class "Default")
      (node (ref "DS2") (pin "2") (pinfunction "K_2") (pintype "passive"))
      (node (ref "R2") (pin "2") (pinfunction "2_2") (pintype "passive"))
    )
    (net (code "82") (name "Net-(DS3-K)") (class "Default")
      (node (ref "DS3") (pin "2") (pinfunction "K_2") (pintype "passive"))
      (node (ref "R3") (pin "2") (pinfunction "2_2") (pintype "passive"))
    )
    (net (code "83") (name "Net-(DS4-K)") (class "Default")
      (node (ref "DS4") (pin "2") (pinfunction "K_2") (pintype "passive"))
      (node (ref "R13") (pin "2") (pinfunction "2_2") (pintype "passive"))
    )
    (net (code "84") (name "Net-(DS5-K)") (class "Default")
      (node (ref "DS5") (pin "2") (pinfunction "K_2") (pintype "passive"))
      (node (ref "R14") (pin "2") (pinfunction "2_2") (pintype "passive"))
    )
    (net (code "85") (name "Net-(DS6-K)") (class "Default")
      (node (ref "DS6") (pin "2") (pinfunction "K_2") (pintype "passive"))
      (node (ref "R15") (pin "2") (pinfunction "2_2") (pintype "passive"))
    )
    (net (code "86") (name "unconnected-(CON1-GNDDefect-Pad9)") (class "Default")
      (node (ref "CON1") (pin "9") (pinfunction "GNDDefect_9") (pintype "power_in"))
    )
    (net (code "87") (name "unconnected-(CON1-KEY-Pad7)") (class "Default")
      (node (ref "CON1") (pin "7") (pinfunction "KEY_7") (pintype "bidirectional"))
    )
  )
)
